# ANA_MCU_CC1310.net
KiCad netlist of a schematic drawn in EAGLE
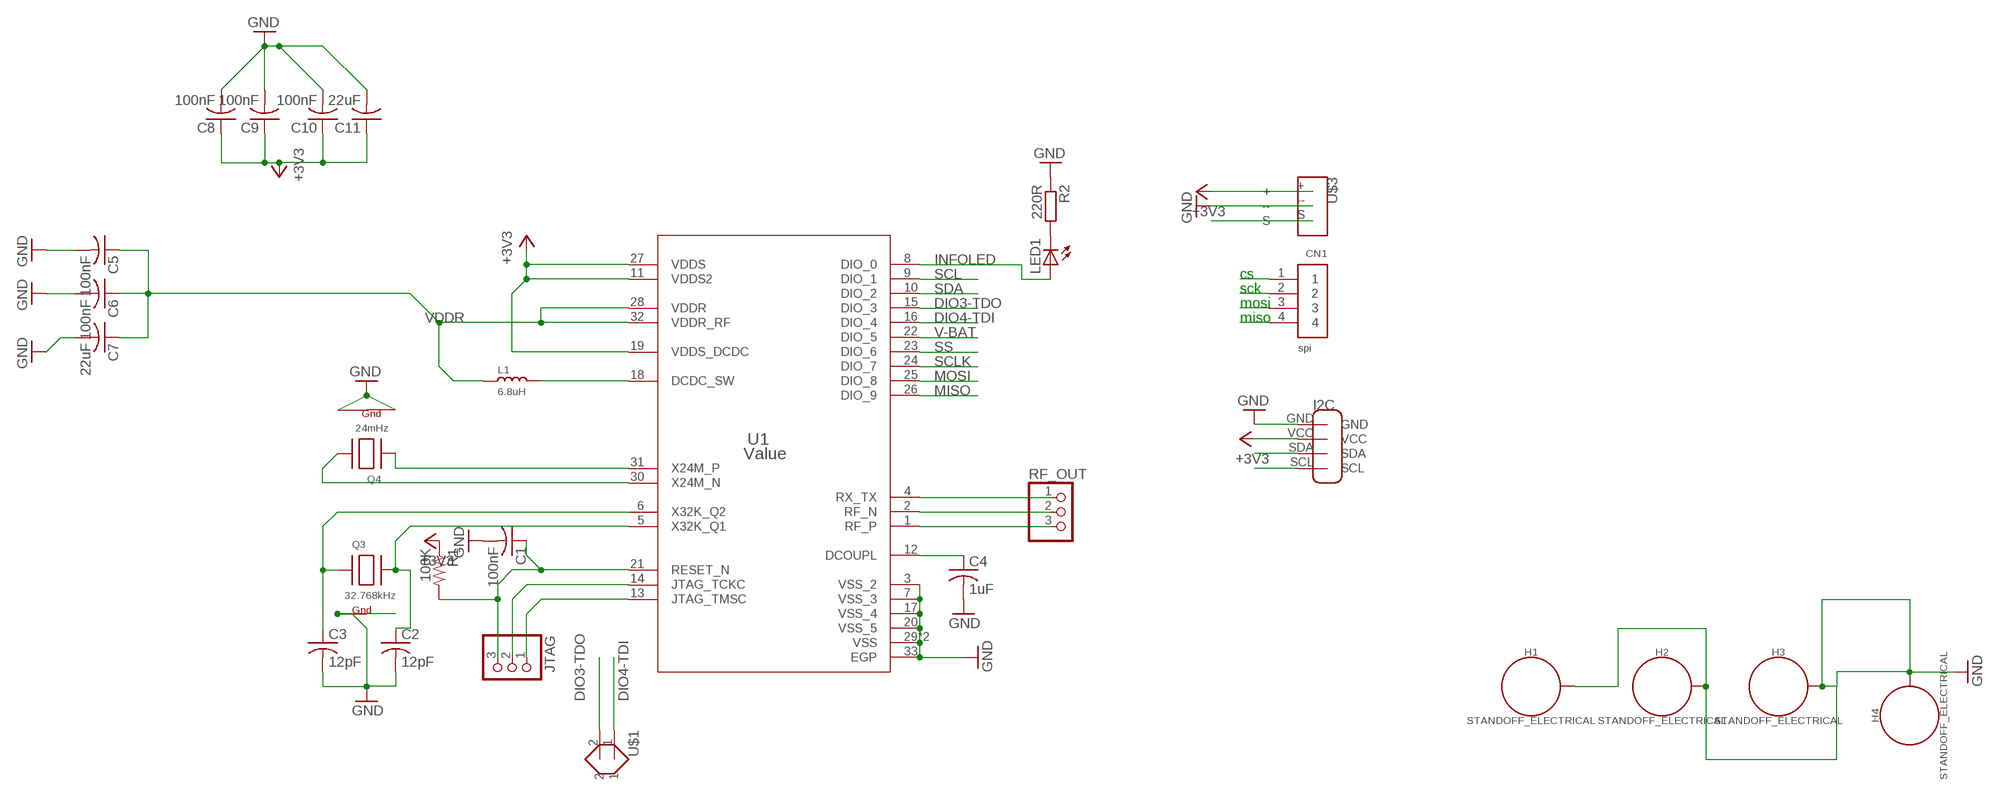
[diagram p0: schematic, sheet 1]

(export (version "E")
  (design (tool "Eeschema 10.0.6"))
  (components
    (comp (ref "C1")
      (value "100nF")
      (footprint "eagle-import:C0805K")
      (libsource (lib "eagle-import") (part "C-USC0805K"))
    )
    (comp (ref "C2")
      (value "12pF")
      (footprint "eagle-import:C0805K")
      (libsource (lib "eagle-import") (part "C-USC0805K"))
    )
    (comp (ref "C3")
      (value "12pF")
      (footprint "eagle-import:C0805K")
      (libsource (lib "eagle-import") (part "C-USC0805K"))
    )
    (comp (ref "C4")
      (value "1uF")
      (footprint "eagle-import:C0805K")
      (libsource (lib "eagle-import") (part "C-USC0805K"))
    )
    (comp (ref "C5")
      (value "100nF")
      (footprint "eagle-import:C0805K")
      (libsource (lib "eagle-import") (part "C-USC0805K"))
    )
    (comp (ref "C6")
      (value "100nF")
      (footprint "eagle-import:C0805K")
      (libsource (lib "eagle-import") (part "C-USC0805K"))
    )
    (comp (ref "C7")
      (value "22uF")
      (footprint "eagle-import:C0805K")
      (libsource (lib "eagle-import") (part "C-USC0805K"))
    )
    (comp (ref "C8")
      (value "100nF")
      (footprint "eagle-import:C0805K")
      (libsource (lib "eagle-import") (part "C-USC0805K"))
    )
    (comp (ref "C9")
      (value "100nF")
      (footprint "eagle-import:C0805K")
      (libsource (lib "eagle-import") (part "C-USC0805K"))
    )
    (comp (ref "C10")
      (value "100nF")
      (footprint "eagle-import:C0805K")
      (libsource (lib "eagle-import") (part "C-USC0805K"))
    )
    (comp (ref "C11")
      (value "22uF")
      (footprint "eagle-import:C0805K")
      (libsource (lib "eagle-import") (part "C-USC0805K"))
    )
    (comp (ref "CN1")
      (value "spi")
      (footprint "eagle-import:1X04-CLEANBIG")
      (libsource (lib "eagle-import") (part "1X4-CLEANBIG"))
    )
    (comp (ref "H1")
      (value "STANDOFF_ELECTRICAL")
      (footprint "eagle-import:STANDOFF-ELECTRICAL")
      (libsource (lib "eagle-import") (part "STANDOFF_ELECTRICAL"))
    )
    (comp (ref "H2")
      (value "STANDOFF_ELECTRICAL")
      (footprint "eagle-import:STANDOFF-ELECTRICAL")
      (libsource (lib "eagle-import") (part "STANDOFF_ELECTRICAL"))
    )
    (comp (ref "H3")
      (value "STANDOFF_ELECTRICAL")
      (footprint "eagle-import:STANDOFF-ELECTRICAL")
      (libsource (lib "eagle-import") (part "STANDOFF_ELECTRICAL"))
    )
    (comp (ref "H4")
      (value "STANDOFF_ELECTRICAL")
      (footprint "eagle-import:STANDOFF-ELECTRICAL")
      (libsource (lib "eagle-import") (part "STANDOFF_ELECTRICAL"))
    )
    (comp (ref "JTAG")
      (value "PINHD-1X3CB")
      (footprint "eagle-import:1X03-CLEANBIG")
      (libsource (lib "eagle-import") (part "PINHD-1X3CB"))
    )
    (comp (ref "L1")
      (value "6.8uH")
      (footprint "eagle-import:L0805")
      (fields (field (name "MPN") "BLM21PG331SN1D"))
      (libsource (lib "eagle-import") (part "SMD-FERRITE-BEAD-330R-1500MA(0805)'0805'"))
    )
    (comp (ref "LED1")
      (value "LEDCHIP-LED0805")
      (footprint "eagle-import:CHIP-LED0805")
      (libsource (lib "eagle-import") (part "LEDCHIP-LED0805"))
    )
    (comp (ref "Q3")
      (value "32.768kHz")
      (footprint "eagle-import:NX3225")
      (libsource (lib "eagle-import") (part "XTAL-4-3225"))
    )
    (comp (ref "Q4")
      (value "24mHz")
      (footprint "eagle-import:NX3225")
      (libsource (lib "eagle-import") (part "XTAL-4-3225"))
    )
    (comp (ref "R1")
      (value "100K")
      (footprint "eagle-import:R0805")
      (libsource (lib "eagle-import") (part "R-US_R0805"))
    )
    (comp (ref "R2")
      (value "220R")
      (footprint "eagle-import:R0805")
      (libsource (lib "eagle-import") (part "R-EU_R0805"))
    )
    (comp (ref "RF_OUT")
      (value "PINHD-1X3CB")
      (footprint "eagle-import:1X03-CLEANBIG")
      (libsource (lib "eagle-import") (part "PINHD-1X3CB"))
    )
    (comp (ref "U$1")
      (value "DCMOTOR")
      (footprint "eagle-import:DCMOTOR")
      (libsource (lib "eagle-import") (part "DCMOTOR"))
    )
    (comp (ref "U$2")
      (value "I2C")
      (footprint "eagle-import:I2C")
      (libsource (lib "eagle-import") (part "I2C"))
    )
    (comp (ref "U$3")
      (value "3PINSENSOR")
      (footprint "eagle-import:3PINSENSOR")
      (libsource (lib "eagle-import") (part "3PINSENSOR"))
    )
    (comp (ref "U1")
      (value "Value")
      (footprint "eagle-import:RSM0032B")
      (fields
        (field (name "ALTERNATEPARTNUMBER") "CC1310F128RSMT")
        (field (name "MANUFACTURER") "Texas Instruments")
        (field (name "PARTNUMBER") "CC1310F128RSMR")
      )
      (libsource (lib "eagle-import") (part "CC1310F128RSMR"))
    )
  )
  (nets
    (net (code "1") (name "+3V3") (class "Default")
      (node (ref "C10") (pin "1") (pinfunction "1_1") (pintype "passive"))
      (node (ref "C11") (pin "1") (pinfunction "1_1") (pintype "passive"))
      (node (ref "C8") (pin "1") (pinfunction "1_1") (pintype "passive"))
      (node (ref "C9") (pin "1") (pinfunction "1_1") (pintype "passive"))
      (node (ref "R1") (pin "1") (pinfunction "1_1") (pintype "passive"))
      (node (ref "U$2") (pin "VCC") (pinfunction "VCC_VCC") (pintype "bidirectional"))
      (node (ref "U$3") (pin "+") (pinfunction "+_+") (pintype "bidirectional"))
      (node (ref "U1") (pin "11") (pinfunction "VDDS2_11") (pintype "power_in"))
      (node (ref "U1") (pin "19") (pinfunction "VDDS_DCDC_19") (pintype "power_in"))
      (node (ref "U1") (pin "27") (pinfunction "VDDS_27") (pintype "power_in"))
    )
    (net (code "2") (name "/DIO3-TDO") (class "Default")
      (node (ref "U$1") (pin "2") (pinfunction "2_2") (pintype "bidirectional"))
      (node (ref "U1") (pin "15") (pinfunction "DIO_3_15") (pintype "bidirectional"))
    )
    (net (code "3") (name "/DIO4-TDI") (class "Default")
      (node (ref "U$1") (pin "1") (pinfunction "1_1") (pintype "bidirectional"))
      (node (ref "U1") (pin "16") (pinfunction "DIO_4_16") (pintype "bidirectional"))
    )
    (net (code "4") (name "/INFOLED") (class "Default")
      (node (ref "LED1") (pin "A") (pinfunction "A_A") (pintype "passive"))
      (node (ref "U1") (pin "8") (pinfunction "DIO_0_8") (pintype "bidirectional"))
    )
    (net (code "5") (name "/MISO") (class "Default")
      (node (ref "CN1") (pin "4") (pinfunction "4_4") (pintype "bidirectional"))
      (node (ref "U1") (pin "26") (pinfunction "DIO_9_26") (pintype "bidirectional"))
    )
    (net (code "6") (name "/MOSI") (class "Default")
      (node (ref "CN1") (pin "3") (pinfunction "3_3") (pintype "bidirectional"))
      (node (ref "U1") (pin "25") (pinfunction "DIO_8_25") (pintype "bidirectional"))
    )
    (net (code "7") (name "/SCL") (class "Default")
      (node (ref "U$2") (pin "SCL") (pinfunction "SCL_SCL") (pintype "bidirectional"))
      (node (ref "U1") (pin "9") (pinfunction "DIO_1_9") (pintype "bidirectional"))
    )
    (net (code "8") (name "/SCLK") (class "Default")
      (node (ref "CN1") (pin "2") (pinfunction "2_2") (pintype "bidirectional"))
      (node (ref "U1") (pin "24") (pinfunction "DIO_7_24") (pintype "bidirectional"))
    )
    (net (code "9") (name "/SDA") (class "Default")
      (node (ref "U$2") (pin "SDA") (pinfunction "SDA_SDA") (pintype "bidirectional"))
      (node (ref "U1") (pin "10") (pinfunction "DIO_2_10") (pintype "bidirectional"))
    )
    (net (code "10") (name "/SS") (class "Default")
      (node (ref "CN1") (pin "1") (pinfunction "1_1") (pintype "bidirectional"))
      (node (ref "U1") (pin "23") (pinfunction "DIO_6_23") (pintype "bidirectional"))
    )
    (net (code "11") (name "/V-BAT") (class "Default")
      (node (ref "U$3") (pin "S") (pinfunction "S_S") (pintype "bidirectional"))
      (node (ref "U1") (pin "22") (pinfunction "DIO_5_22") (pintype "bidirectional"))
    )
    (net (code "12") (name "/VDDR") (class "Default")
      (node (ref "C5") (pin "1") (pinfunction "1_1") (pintype "passive"))
      (node (ref "C6") (pin "1") (pinfunction "1_1") (pintype "passive"))
      (node (ref "C7") (pin "1") (pinfunction "1_1") (pintype "passive"))
      (node (ref "L1") (pin "1") (pinfunction "1_1") (pintype "passive"))
      (node (ref "U1") (pin "28") (pinfunction "VDDR_28") (pintype "power_in"))
      (node (ref "U1") (pin "32") (pinfunction "VDDR_RF_32") (pintype "power_in"))
    )
    (net (code "13") (name "GND") (class "Default")
      (node (ref "C1") (pin "2") (pinfunction "2_2") (pintype "passive"))
      (node (ref "C10") (pin "2") (pinfunction "2_2") (pintype "passive"))
      (node (ref "C11") (pin "2") (pinfunction "2_2") (pintype "passive"))
      (node (ref "C2") (pin "2") (pinfunction "2_2") (pintype "passive"))
      (node (ref "C3") (pin "2") (pinfunction "2_2") (pintype "passive"))
      (node (ref "C4") (pin "2") (pinfunction "2_2") (pintype "passive"))
      (node (ref "C5") (pin "2") (pinfunction "2_2") (pintype "passive"))
      (node (ref "C6") (pin "2") (pinfunction "2_2") (pintype "passive"))
      (node (ref "C7") (pin "2") (pinfunction "2_2") (pintype "passive"))
      (node (ref "C8") (pin "2") (pinfunction "2_2") (pintype "passive"))
      (node (ref "C9") (pin "2") (pinfunction "2_2") (pintype "passive"))
      (node (ref "H1") (pin "P1") (pinfunction "P$1_P1") (pintype "bidirectional"))
      (node (ref "H2") (pin "P1") (pinfunction "P$1_P1") (pintype "bidirectional"))
      (node (ref "H3") (pin "P1") (pinfunction "P$1_P1") (pintype "bidirectional"))
      (node (ref "H4") (pin "P1") (pinfunction "P$1_P1") (pintype "bidirectional"))
      (node (ref "Q3") (pin "2") (pinfunction "G2_2") (pintype "power_in"))
      (node (ref "Q3") (pin "4") (pinfunction "G1_4") (pintype "power_in"))
      (node (ref "Q4") (pin "2") (pinfunction "G2_2") (pintype "power_in"))
      (node (ref "Q4") (pin "4") (pinfunction "G1_4") (pintype "power_in"))
      (node (ref "R2") (pin "1") (pinfunction "1_1") (pintype "passive"))
      (node (ref "U$2") (pin "GND") (pinfunction "GND_GND") (pintype "bidirectional"))
      (node (ref "U$3") (pin "--") (pinfunction "--_--") (pintype "bidirectional"))
      (node (ref "U1") (pin "17") (pinfunction "VSS_4_17") (pintype "power_in"))
      (node (ref "U1") (pin "20") (pinfunction "VSS_5_20") (pintype "power_in"))
      (node (ref "U1") (pin "29") (pinfunction "VSS_29") (pintype "power_in"))
      (node (ref "U1") (pin "3") (pinfunction "VSS_2_3") (pintype "power_in"))
      (node (ref "U1") (pin "33") (pinfunction "EGP_33") (pintype "power_in"))
      (node (ref "U1") (pin "7") (pinfunction "VSS_3_7") (pintype "power_in"))
      (node (ref "U1") (pin "V") (pinfunction "VSS_V") (pintype "power_in"))
    )
    (net (code "14") (name "Net-(LED1-PadC)") (class "Default")
      (node (ref "LED1") (pin "C") (pinfunction "C_C") (pintype "passive"))
      (node (ref "R2") (pin "2") (pinfunction "2_2") (pintype "passive"))
    )
    (net (code "15") (name "Net-(Q3-X1)") (class "Default")
      (node (ref "C3") (pin "1") (pinfunction "1_1") (pintype "passive"))
      (node (ref "Q3") (pin "1") (pinfunction "X1_1") (pintype "bidirectional"))
      (node (ref "U1") (pin "6") (pinfunction "X32K_Q2_6") (pintype "output"))
    )
    (net (code "16") (name "Net-(Q3-X2)") (class "Default")
      (node (ref "C2") (pin "1") (pinfunction "1_1") (pintype "passive"))
      (node (ref "Q3") (pin "3") (pinfunction "X2_3") (pintype "bidirectional"))
      (node (ref "U1") (pin "5") (pinfunction "X32K_Q1_5") (pintype "output"))
    )
    (net (code "17") (name "Net-(Q4-X1)") (class "Default")
      (node (ref "Q4") (pin "1") (pinfunction "X1_1") (pintype "bidirectional"))
      (node (ref "U1") (pin "31") (pinfunction "X24M_P_31") (pintype "passive"))
    )
    (net (code "18") (name "Net-(Q4-X2)") (class "Default")
      (node (ref "Q4") (pin "3") (pinfunction "X2_3") (pintype "bidirectional"))
      (node (ref "U1") (pin "30") (pinfunction "X24M_N_30") (pintype "passive"))
    )
    (net (code "19") (name "Net-(U1-DCDC_SW)") (class "Default")
      (node (ref "L1") (pin "2") (pinfunction "2_2") (pintype "passive"))
      (node (ref "U1") (pin "18") (pinfunction "DCDC_SW_18") (pintype "power_in"))
    )
    (net (code "20") (name "Net-(U1-DCOUPL)") (class "Default")
      (node (ref "C4") (pin "1") (pinfunction "1_1") (pintype "passive"))
      (node (ref "U1") (pin "12") (pinfunction "DCOUPL_12") (pintype "passive"))
    )
    (net (code "21") (name "Net-(U1-JTAG_TCKC)") (class "Default")
      (node (ref "JTAG") (pin "2") (pinfunction "2_2") (pintype "passive"))
      (node (ref "U1") (pin "14") (pinfunction "JTAG_TCKC_14") (pintype "passive"))
    )
    (net (code "22") (name "Net-(U1-JTAG_TMSC)") (class "Default")
      (node (ref "JTAG") (pin "1") (pinfunction "1_1") (pintype "passive"))
      (node (ref "U1") (pin "13") (pinfunction "JTAG_TMSC_13") (pintype "passive"))
    )
    (net (code "23") (name "Net-(U1-RESET_N)") (class "Default")
      (node (ref "C1") (pin "1") (pinfunction "1_1") (pintype "passive"))
      (node (ref "JTAG") (pin "3") (pinfunction "3_3") (pintype "passive"))
      (node (ref "R1") (pin "2") (pinfunction "2_2") (pintype "passive"))
      (node (ref "U1") (pin "21") (pinfunction "RESET_N_21") (pintype "input"))
    )
    (net (code "24") (name "Net-(U1-RF_N)") (class "Default")
      (node (ref "RF_OUT") (pin "2") (pinfunction "2_2") (pintype "passive"))
      (node (ref "U1") (pin "2") (pinfunction "RF_N_2") (pintype "bidirectional"))
    )
    (net (code "25") (name "Net-(U1-RF_P)") (class "Default")
      (node (ref "RF_OUT") (pin "3") (pinfunction "3_3") (pintype "passive"))
      (node (ref "U1") (pin "1") (pinfunction "RF_P_1") (pintype "bidirectional"))
    )
    (net (code "26") (name "Net-(U1-RX_TX)") (class "Default")
      (node (ref "RF_OUT") (pin "1") (pinfunction "1_1") (pintype "passive"))
      (node (ref "U1") (pin "4") (pinfunction "RX_TX_4") (pintype "input"))
    )
  )
)
